# pwr_pos_lm317.net
KiCad netlist of a schematic drawn in EAGLE
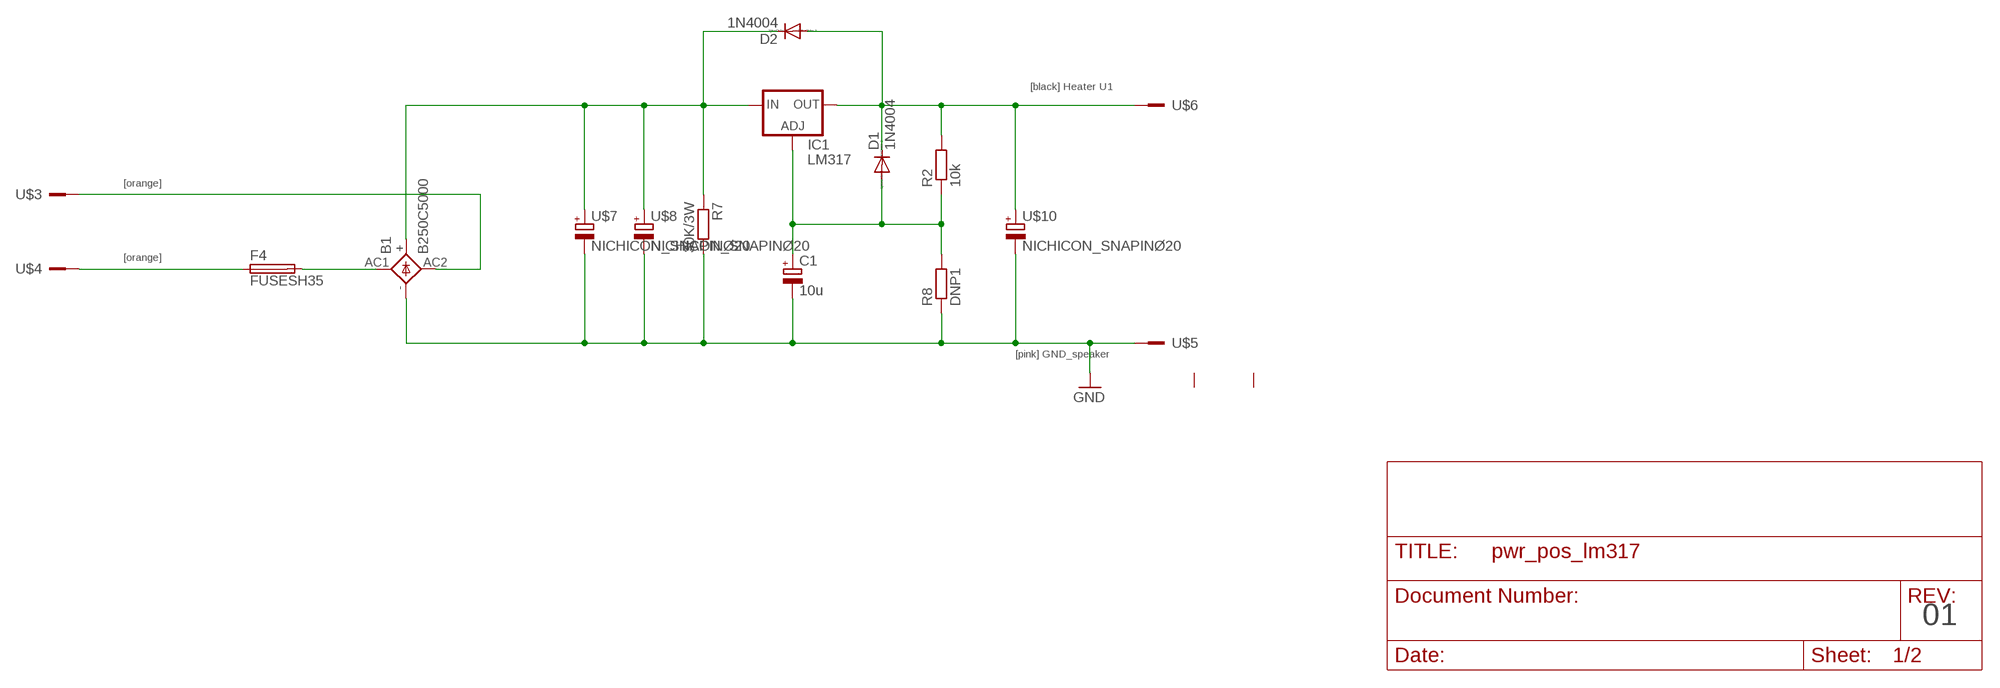
[diagram p0: schematic, sheet 1]

(export (version "E")
  (design (tool "Eeschema 10.0.6"))
  (components
    (comp (ref "B1")
      (value "B250C5000")
      (footprint "eagle-import:DIOTEC_BC5000")
      (libsource (lib "eagle-import") (part "DIOTEC_BC5000"))
    )
    (comp (ref "C1")
      (value "10u")
      (footprint "eagle-import:E2,5-6E")
      (libsource (lib "eagle-import") (part "CPOL-EUE2,5-6E"))
    )
    (comp (ref "D1")
      (value "1N4004")
      (footprint "eagle-import:DO41-10")
      (libsource (lib "eagle-import") (part "1N4004"))
    )
    (comp (ref "D2")
      (value "1N4004")
      (footprint "eagle-import:DO41-10")
      (libsource (lib "eagle-import") (part "1N4004"))
    )
    (comp (ref "F4")
      (value "FUSESH35")
      (footprint "eagle-import:SH25")
      (libsource (lib "eagle-import") (part "FUSESH35"))
    )
    (comp (ref "IC1")
      (value "LM317")
      (footprint "eagle-import:317TS")
      (libsource (lib "eagle-import") (part "LM317TS"))
    )
    (comp (ref "R2")
      (value "10k")
      (footprint "eagle-import:0411_12")
      (libsource (lib "eagle-import") (part "R-EU_0411/12"))
    )
    (comp (ref "R7")
      (value "30K/3W")
      (footprint "eagle-import:0922V")
      (libsource (lib "eagle-import") (part "R-EU_0922V"))
    )
    (comp (ref "R8")
      (value "DNP1")
      (footprint "eagle-import:0411_12")
      (libsource (lib "eagle-import") (part "R-EU_0411/12"))
    )
    (comp (ref "U$1")
      (value "SK456-60-3XM3L")
      (footprint "eagle-import:SK456-60-3XM3L")
      (libsource (lib "eagle-import") (part "SK456-60-3XM3L"))
    )
    (comp (ref "U$2")
      (value "RN_POWER")
      (footprint "eagle-import:RN")
      (libsource (lib "eagle-import") (part "RN_POWER"))
    )
    (comp (ref "U$3")
      (value "M1")
      (footprint "eagle-import:M1_OFFSET")
      (libsource (lib "eagle-import") (part "M1"))
    )
    (comp (ref "U$4")
      (value "M1")
      (footprint "eagle-import:M1_OFFSET")
      (libsource (lib "eagle-import") (part "M1"))
    )
    (comp (ref "U$5")
      (value "M1")
      (footprint "eagle-import:M1_OFFSET")
      (libsource (lib "eagle-import") (part "M1"))
    )
    (comp (ref "U$6")
      (value "M1")
      (footprint "eagle-import:M1_OFFSET")
      (libsource (lib "eagle-import") (part "M1"))
    )
    (comp (ref "U$7")
      (value "NICHICON_SNAPINØ20")
      (footprint "eagle-import:C_20G10")
      (libsource (lib "eagle-import") (part "NICHICON_SNAPINØ20"))
    )
    (comp (ref "U$8")
      (value "NICHICON_SNAPINØ20")
      (footprint "eagle-import:C_20G10")
      (libsource (lib "eagle-import") (part "NICHICON_SNAPINØ20"))
    )
    (comp (ref "U$10")
      (value "NICHICON_SNAPINØ20")
      (footprint "eagle-import:C_20G10")
      (libsource (lib "eagle-import") (part "NICHICON_SNAPINØ20"))
    )
  )
  (nets
    (net (code "1") (name "GND") (class "Default")
      (node (ref "B1") (pin "-") (pinfunction "-_-") (pintype "passive"))
      (node (ref "C1") (pin "-") (pinfunction "-_-") (pintype "passive"))
      (node (ref "R7") (pin "2") (pinfunction "2_2") (pintype "passive"))
      (node (ref "R8") (pin "1") (pinfunction "1_1") (pintype "passive"))
      (node (ref "U$10") (pin "-") (pinfunction "-_-") (pintype "passive"))
      (node (ref "U$5") (pin "1") (pinfunction "KL_1") (pintype "passive"))
      (node (ref "U$7") (pin "-") (pinfunction "-_-") (pintype "passive"))
      (node (ref "U$8") (pin "-") (pinfunction "-_-") (pintype "passive"))
    )
    (net (code "2") (name "Net-(B1-PadAC1)") (class "Default")
      (node (ref "B1") (pin "AC1") (pinfunction "AC1_AC1") (pintype "passive"))
      (node (ref "F4") (pin "2") (pinfunction "2_2") (pintype "passive"))
    )
    (net (code "3") (name "Net-(IC1-ADJ)") (class "Default")
      (node (ref "C1") (pin "+") (pinfunction "+_+") (pintype "passive"))
      (node (ref "D1") (pin "A") (pinfunction "A_A") (pintype "passive"))
      (node (ref "IC1") (pin "1") (pinfunction "ADJ_1") (pintype "input"))
      (node (ref "R2") (pin "1") (pinfunction "1_1") (pintype "passive"))
      (node (ref "R8") (pin "2") (pinfunction "2_2") (pintype "passive"))
    )
    (net (code "4") (name "Net-(IC1-IN)") (class "Default")
      (node (ref "B1") (pin "+") (pinfunction "+_+") (pintype "passive"))
      (node (ref "D2") (pin "C") (pinfunction "C_C") (pintype "passive"))
      (node (ref "IC1") (pin "3") (pinfunction "IN_3") (pintype "input"))
      (node (ref "R7") (pin "1") (pinfunction "1_1") (pintype "passive"))
      (node (ref "U$7") (pin "+") (pinfunction "+_+") (pintype "passive"))
      (node (ref "U$8") (pin "+") (pinfunction "+_+") (pintype "passive"))
    )
    (net (code "5") (name "Net-(IC1-OUT)") (class "Default")
      (node (ref "D1") (pin "C") (pinfunction "C_C") (pintype "passive"))
      (node (ref "D2") (pin "A") (pinfunction "A_A") (pintype "passive"))
      (node (ref "IC1") (pin "2") (pinfunction "OUT_2") (pintype "passive"))
      (node (ref "R2") (pin "2") (pinfunction "2_2") (pintype "passive"))
      (node (ref "U$10") (pin "+") (pinfunction "+_+") (pintype "passive"))
      (node (ref "U$6") (pin "1") (pinfunction "KL_1") (pintype "passive"))
    )
    (net (code "6") (name "Net-(U$3-KL)") (class "Default")
      (node (ref "B1") (pin "AC2") (pinfunction "AC2_AC2") (pintype "passive"))
      (node (ref "U$3") (pin "1") (pinfunction "KL_1") (pintype "passive"))
    )
    (net (code "7") (name "Net-(U$4-KL)") (class "Default")
      (node (ref "F4") (pin "1") (pinfunction "1_1") (pintype "passive"))
      (node (ref "U$4") (pin "1") (pinfunction "KL_1") (pintype "passive"))
    )
    (net (code "8") (name "unconnected-(U$1-PadP$1)") (class "Default")
      (node (ref "U$1") (pin "P$1") (pinfunction "P$1_P$1") (pintype "no_connect"))
    )
    (net (code "9") (name "unconnected-(U$1-PadP$2)") (class "Default")
      (node (ref "U$1") (pin "P$2") (pinfunction "P$2_P$2") (pintype "no_connect"))
    )
    (net (code "10") (name "unconnected-(U$2-P$1-PadSH@1)") (class "Default")
      (node (ref "U$2") (pin "SH@1") (pinfunction "P$1_SH@1") (pintype "no_connect"))
    )
    (net (code "11") (name "unconnected-(U$2-P$2-PadSH@2)") (class "Default")
      (node (ref "U$2") (pin "SH@2") (pinfunction "P$2_SH@2") (pintype "no_connect"))
    )
    (net (code "12") (name "unconnected-(U$2-P$3-PadSH@3)") (class "Default")
      (node (ref "U$2") (pin "SH@3") (pinfunction "P$3_SH@3") (pintype "no_connect"))
    )
    (net (code "13") (name "unconnected-(U$2-P$4-PadSH@4)") (class "Default")
      (node (ref "U$2") (pin "SH@4") (pinfunction "P$4_SH@4") (pintype "no_connect"))
    )
  )
)
